# ESP32-PCB-Antenna-USB-Dongle-Motion-Sens.net
KiCad netlist of a schematic drawn in Altium Designer
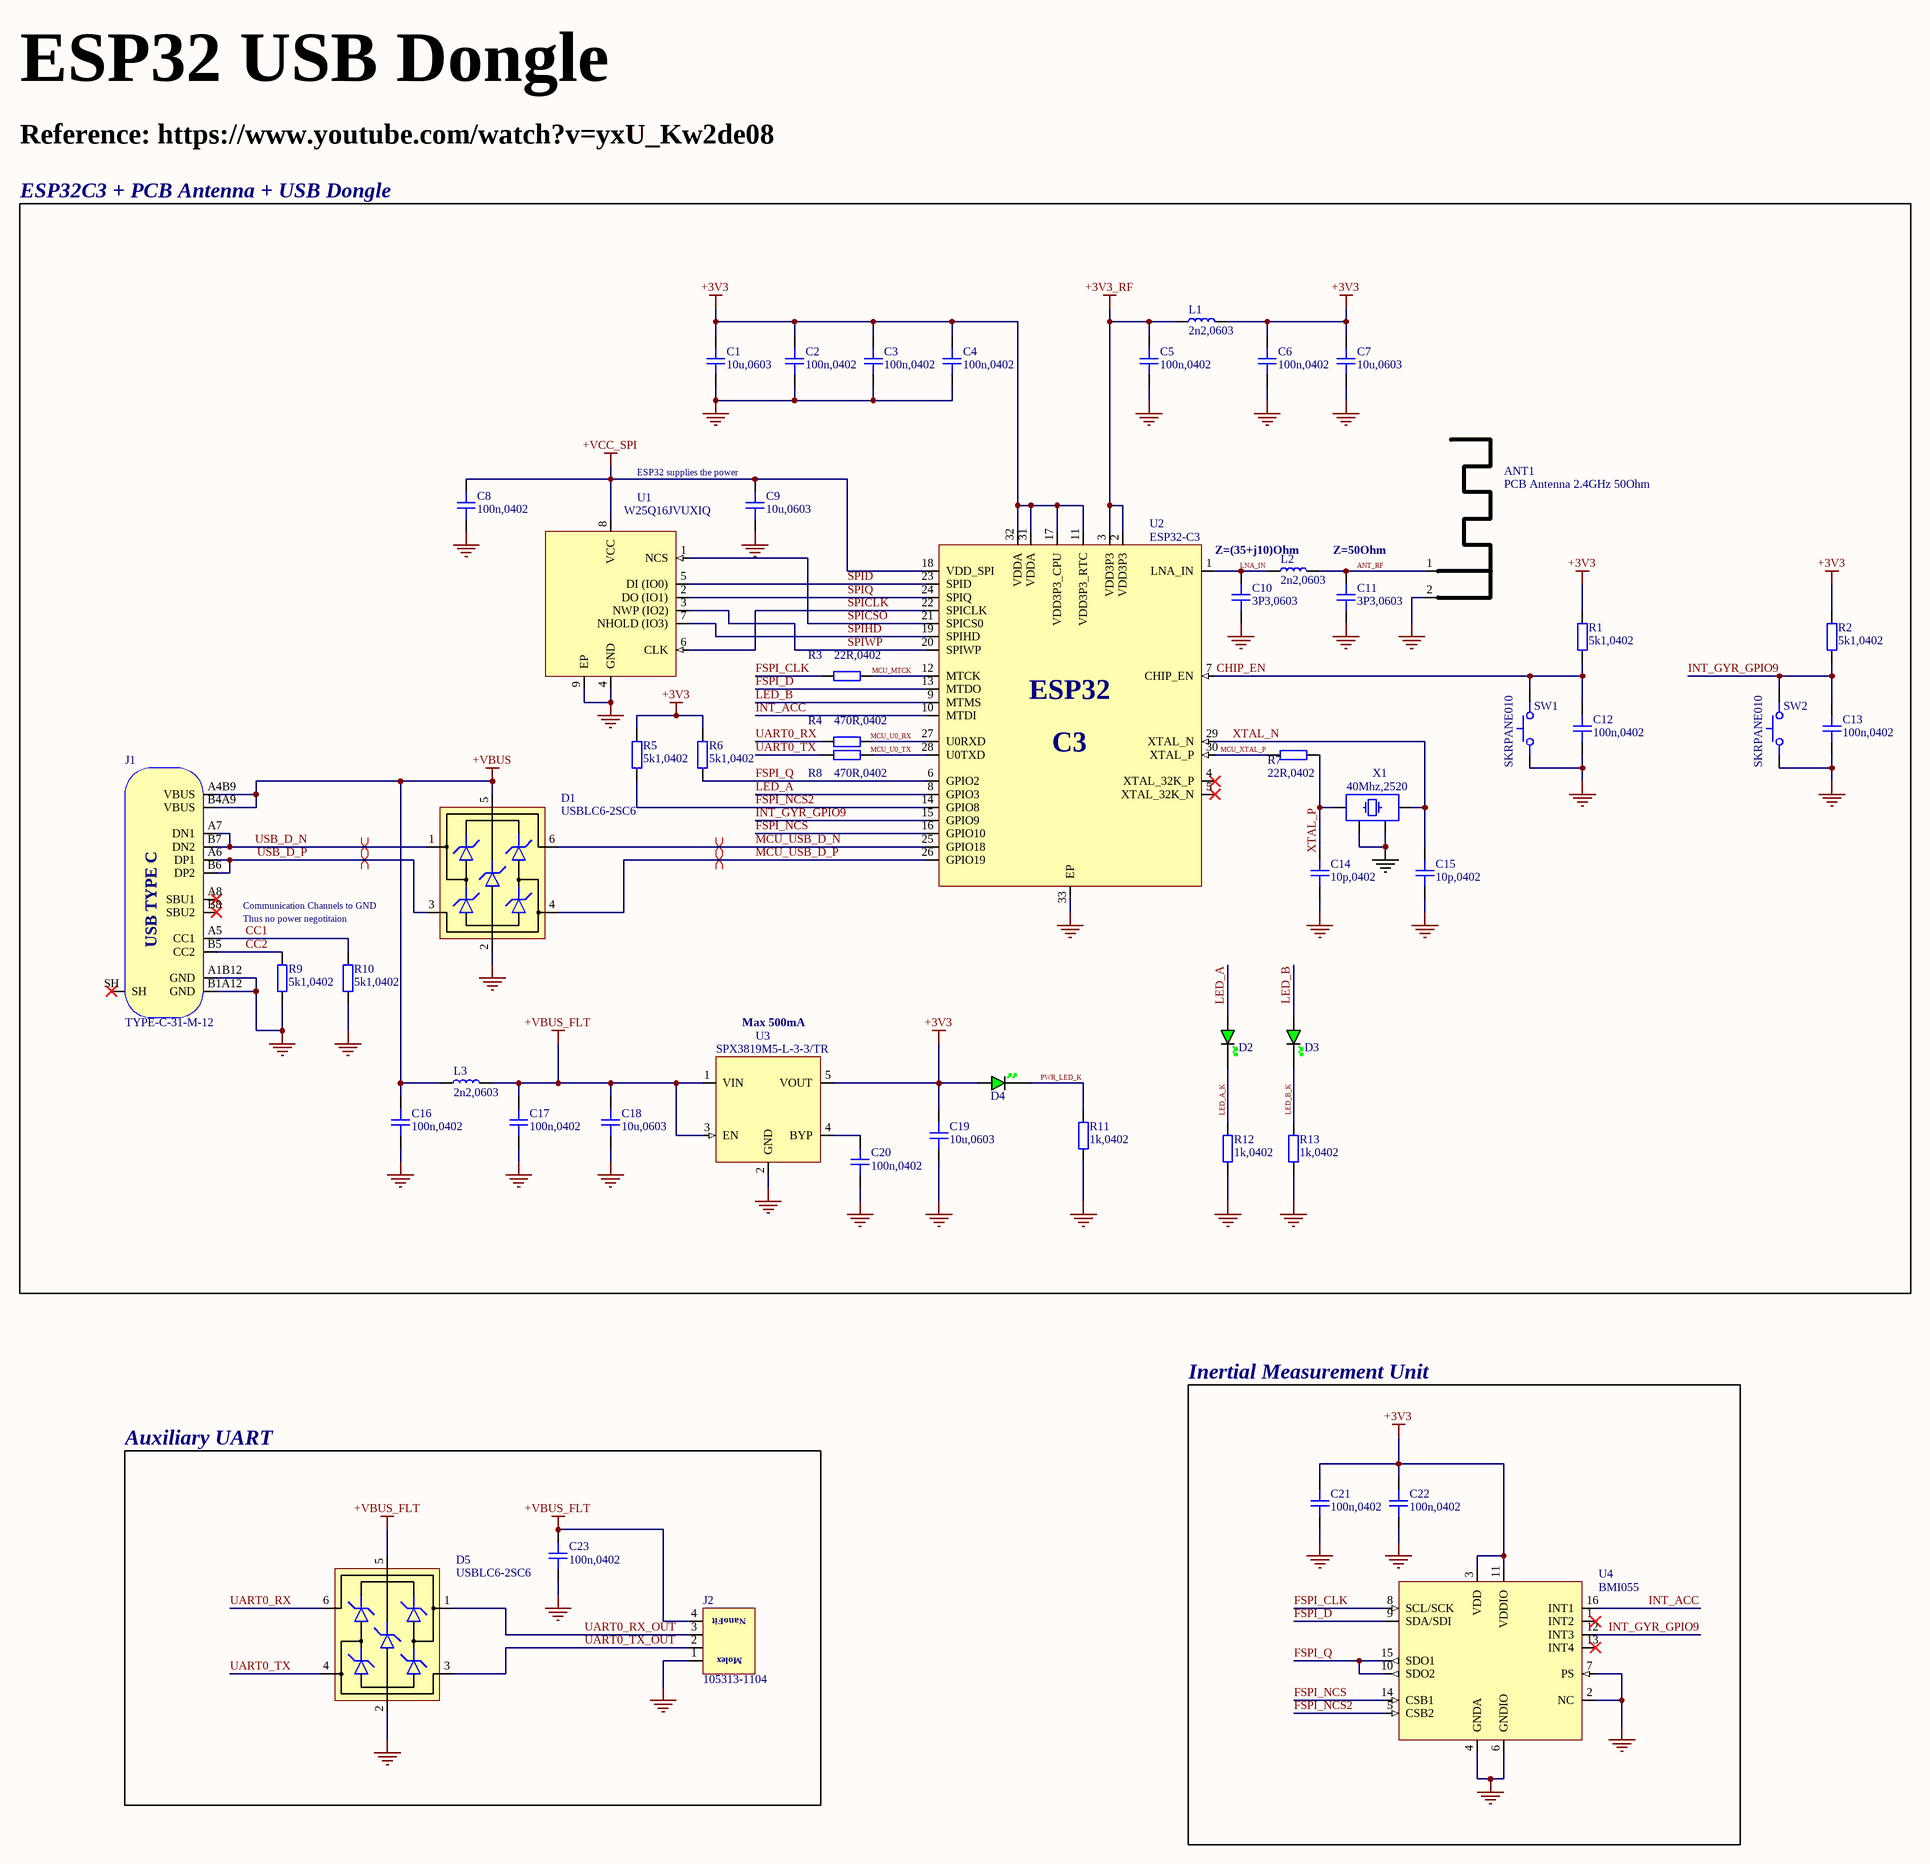
[diagram p0: ESP32-PCB-Antenna-USB-Dongle-Motion-Sensor.SchDoc]

(export (version "E")
  (design (tool "Eeschema 10.0.6"))
  (components
    (comp (ref "ANT1")
      (value "PCB Antenna 2.4GHz 50Ohm")
      (footprint "ANT_IFA_USB_2_4GHZ_50R")
      (description "Inverted F 2.4GHz ISM PCB Antenna 50 Ohm")
      (libsource (lib "Schematic-Lib-PhilsLab") (part "ANT_IFA_USB_2_4GHZ_50R"))
    )
    (comp (ref "C1")
      (value "10u,0603")
      (footprint "CAP_0603")
      (description "Capacitor SMD 0603 25V")
      (libsource (lib "Schematic-Lib-PhilsLab") (part "CAP_0603_25V"))
    )
    (comp (ref "C2")
      (value "100n,0402")
      (footprint "CAP_0402")
      (description "Capacitor SMD 0402 16V")
      (libsource (lib "Schematic-Lib-PhilsLab") (part "CAP_0402_16V"))
    )
    (comp (ref "C3")
      (value "100n,0402")
      (footprint "CAP_0402")
      (description "Capacitor SMD 0402 16V")
      (libsource (lib "Schematic-Lib-PhilsLab") (part "CAP_0402_16V"))
    )
    (comp (ref "C4")
      (value "100n,0402")
      (footprint "CAP_0402")
      (description "Capacitor SMD 0402 16V")
      (libsource (lib "Schematic-Lib-PhilsLab") (part "CAP_0402_16V"))
    )
    (comp (ref "C5")
      (value "100n,0402")
      (footprint "CAP_0402")
      (description "Capacitor SMD 0402 16V")
      (libsource (lib "Schematic-Lib-PhilsLab") (part "CAP_0402_16V"))
    )
    (comp (ref "C6")
      (value "100n,0402")
      (footprint "CAP_0402")
      (description "Capacitor SMD 0402 16V")
      (libsource (lib "Schematic-Lib-PhilsLab") (part "CAP_0402_16V"))
    )
    (comp (ref "C7")
      (value "10u,0603")
      (footprint "CAP_0603")
      (description "Capacitor SMD 0603 25V")
      (libsource (lib "Schematic-Lib-PhilsLab") (part "CAP_0603_25V"))
    )
    (comp (ref "C8")
      (value "100n,0402")
      (footprint "CAP_0402")
      (description "Capacitor SMD 0402 16V")
      (libsource (lib "Schematic-Lib-PhilsLab") (part "CAP_0402_16V"))
    )
    (comp (ref "C9")
      (value "10u,0603")
      (footprint "CAP_0603")
      (description "Capacitor SMD 0603 25V")
      (libsource (lib "Schematic-Lib-PhilsLab") (part "CAP_0603_25V"))
    )
    (comp (ref "C10")
      (value "3P3,0603")
      (footprint "CAP_0603")
      (description "Capacitor SMD 0603 25V")
      (libsource (lib "Schematic-Lib-PhilsLab") (part "CAP_0603_25V"))
    )
    (comp (ref "C11")
      (value "3P3,0603")
      (footprint "CAP_0603")
      (description "Capacitor SMD 0603 25V")
      (libsource (lib "Schematic-Lib-PhilsLab") (part "CAP_0603_25V"))
    )
    (comp (ref "C12")
      (value "100n,0402")
      (footprint "CAP_0402")
      (description "Capacitor SMD 0402 16V")
      (libsource (lib "Schematic-Lib-PhilsLab") (part "CAP_0402_16V"))
    )
    (comp (ref "C13")
      (value "100n,0402")
      (footprint "CAP_0402")
      (description "Capacitor SMD 0402 16V")
      (libsource (lib "Schematic-Lib-PhilsLab") (part "CAP_0402_16V"))
    )
    (comp (ref "C14")
      (value "10p,0402")
      (footprint "CAP_0402")
      (description "Capacitor SMD 0402 16V")
      (libsource (lib "Schematic-Lib-PhilsLab") (part "CAP_0402_16V"))
    )
    (comp (ref "C15")
      (value "10p,0402")
      (footprint "CAP_0402")
      (description "Capacitor SMD 0402 16V")
      (libsource (lib "Schematic-Lib-PhilsLab") (part "CAP_0402_16V"))
    )
    (comp (ref "C16")
      (value "100n,0402")
      (footprint "CAP_0402")
      (description "Capacitor SMD 0402 16V")
      (libsource (lib "Schematic-Lib-PhilsLab") (part "CAP_0402_16V"))
    )
    (comp (ref "C17")
      (value "100n,0402")
      (footprint "CAP_0402")
      (description "Capacitor SMD 0402 16V")
      (libsource (lib "Schematic-Lib-PhilsLab") (part "CAP_0402_16V"))
    )
    (comp (ref "C18")
      (value "10u,0603")
      (footprint "CAP_0603")
      (description "Capacitor SMD 0603 25V")
      (libsource (lib "Schematic-Lib-PhilsLab") (part "CAP_0603_25V"))
    )
    (comp (ref "C19")
      (value "10u,0603")
      (footprint "CAP_0603")
      (description "Capacitor SMD 0603 25V")
      (libsource (lib "Schematic-Lib-PhilsLab") (part "CAP_0603_25V"))
    )
    (comp (ref "C20")
      (value "100n,0402")
      (footprint "CAP_0402")
      (description "Capacitor SMD 0402 16V")
      (libsource (lib "Schematic-Lib-PhilsLab") (part "CAP_0402_16V"))
    )
    (comp (ref "C21")
      (value "100n,0402")
      (footprint "CAP_0402")
      (description "Capacitor SMD 0402 16V")
      (libsource (lib "Schematic-Lib-PhilsLab") (part "CAP_0402_16V"))
    )
    (comp (ref "C22")
      (value "100n,0402")
      (footprint "CAP_0402")
      (description "Capacitor SMD 0402 16V")
      (libsource (lib "Schematic-Lib-PhilsLab") (part "CAP_0402_16V"))
    )
    (comp (ref "C23")
      (value "100n,0402")
      (footprint "CAP_0402")
      (description "Capacitor SMD 0402 16V")
      (libsource (lib "Schematic-Lib-PhilsLab") (part "CAP_0402_16V"))
    )
    (comp (ref "D1")
      (value "USBLC6-2SC6")
      (footprint "SOT-23-6")
      (description "Low-Capacitance ESD Protection USB")
      (fields (field (name "MANUFACTURER") "STMicroelectronics"))
      (libsource (lib "") (part "USBLC6-2SC6_1"))
    )
    (comp (ref "D2")
      (value "GREEN")
      (footprint "LED_0402_GREEN")
      (description "LED 0402 GREEN SMD")
      (libsource (lib "Schematic-Lib-PhilsLab") (part "LED_0402_GREEN"))
    )
    (comp (ref "D3")
      (value "GREEN")
      (footprint "LED_0402_GREEN")
      (description "LED 0402 GREEN SMD")
      (libsource (lib "Schematic-Lib-PhilsLab") (part "LED_0402_GREEN"))
    )
    (comp (ref "D4")
      (value "GREEN")
      (footprint "LED_0402_GREEN")
      (description "LED 0402 GREEN SMD")
      (libsource (lib "Schematic-Lib-PhilsLab") (part "LED_0402_GREEN"))
    )
    (comp (ref "D5")
      (value "USBLC6-2SC6")
      (footprint "SOT-23-6")
      (description "Low-Capacitance ESD Protection USB")
      (fields (field (name "MANUFACTURER") "STMicroelectronics"))
      (libsource (lib "Schematic-Lib-PhilsLab") (part "USBLC6-2SC6"))
    )
    (comp (ref "J1")
      (value "TYPE-C-31-M-12")
      (footprint "TYPE-C-31-M-12")
      (description "USB Type C Connector Horizontal SMT")
      (fields (field (name "MANUFACTURER") "Koren Hroparts"))
      (libsource (lib "Schematic-Lib-PhilsLab") (part "TYPE-C-31-M-12"))
    )
    (comp (ref "J2")
      (value "105313-1104")
      (footprint "105313-1104")
      (fields (field (name "MANUFACTURER") "Molex"))
      (libsource (lib "Schematic-Lib-PhilsLab") (part "105313-1104"))
    )
    (comp (ref "L1")
      (value "2n2,0603")
      (footprint "IND_0603")
      (description "Inductor SMD 0603")
      (libsource (lib "Schematic-Lib-PhilsLab") (part "IND_0603"))
    )
    (comp (ref "L2")
      (value "2n2,0603")
      (footprint "IND_0603")
      (description "Inductor SMD 0603")
      (libsource (lib "Schematic-Lib-PhilsLab") (part "IND_0603"))
    )
    (comp (ref "L3")
      (value "2n2,0603")
      (footprint "IND_0603")
      (description "Inductor SMD 0603")
      (libsource (lib "Schematic-Lib-PhilsLab") (part "IND_0603"))
    )
    (comp (ref "R1")
      (value "5k1,0402")
      (footprint "RES_0402")
      (description "Resistor SMD 0402")
      (libsource (lib "Schematic-Lib-PhilsLab") (part "RES_0402"))
    )
    (comp (ref "R2")
      (value "5k1,0402")
      (footprint "RES_0402")
      (description "Resistor SMD 0402")
      (libsource (lib "Schematic-Lib-PhilsLab") (part "RES_0402"))
    )
    (comp (ref "R3")
      (value "22R,0402")
      (footprint "RES_0402")
      (description "Resistor SMD 0402")
      (libsource (lib "Schematic-Lib-PhilsLab") (part "RES_0402"))
    )
    (comp (ref "R4")
      (value "470R,0402")
      (footprint "RES_0402")
      (description "Resistor SMD 0402")
      (libsource (lib "Schematic-Lib-PhilsLab") (part "RES_0402"))
    )
    (comp (ref "R5")
      (value "5k1,0402")
      (footprint "RES_0402")
      (description "Resistor SMD 0402")
      (libsource (lib "Schematic-Lib-PhilsLab") (part "RES_0402"))
    )
    (comp (ref "R6")
      (value "5k1,0402")
      (footprint "RES_0402")
      (description "Resistor SMD 0402")
      (libsource (lib "Schematic-Lib-PhilsLab") (part "RES_0402"))
    )
    (comp (ref "R7")
      (value "22R,0402")
      (footprint "RES_0402")
      (description "Resistor SMD 0402")
      (libsource (lib "Schematic-Lib-PhilsLab") (part "RES_0402"))
    )
    (comp (ref "R8")
      (value "470R,0402")
      (footprint "RES_0402")
      (description "Resistor SMD 0402")
      (libsource (lib "Schematic-Lib-PhilsLab") (part "RES_0402"))
    )
    (comp (ref "R9")
      (value "5k1,0402")
      (footprint "RES_0402")
      (description "Resistor SMD 0402")
      (libsource (lib "Schematic-Lib-PhilsLab") (part "RES_0402"))
    )
    (comp (ref "R10")
      (value "5k1,0402")
      (footprint "RES_0402")
      (description "Resistor SMD 0402")
      (libsource (lib "Schematic-Lib-PhilsLab") (part "RES_0402"))
    )
    (comp (ref "R11")
      (value "1k,0402")
      (footprint "RES_0402")
      (description "Resistor SMD 0402")
      (libsource (lib "Schematic-Lib-PhilsLab") (part "RES_0402"))
    )
    (comp (ref "R12")
      (value "1k,0402")
      (footprint "RES_0402")
      (description "Resistor SMD 0402")
      (libsource (lib "Schematic-Lib-PhilsLab") (part "RES_0402"))
    )
    (comp (ref "R13")
      (value "1k,0402")
      (footprint "RES_0402")
      (description "Resistor SMD 0402")
      (libsource (lib "Schematic-Lib-PhilsLab") (part "RES_0402"))
    )
    (comp (ref "SW1")
      (value "SKRPANE010")
      (footprint "SKRPANE010")
      (description "Tactile Switch SMD SPST")
      (fields (field (name "MANUFACTURER") "Alps Alpine"))
      (libsource (lib "Schematic-Lib-PhilsLab") (part "SKRPANE010"))
    )
    (comp (ref "SW2")
      (value "SKRPANE010")
      (footprint "SKRPANE010")
      (description "Tactile Switch SMD SPST")
      (fields (field (name "MANUFACTURER") "Alps Alpine"))
      (libsource (lib "Schematic-Lib-PhilsLab") (part "SKRPANE010"))
    )
    (comp (ref "U1")
      (value "W25Q16JVUXIQ")
      (footprint "USON-8-2X3MM")
      (description "16M-BIT SERIAL FLASH MEMORY WITH DUAL/QUAD SPI USON-8")
      (fields (field (name "MANUFACTURER") "Winbond"))
      (libsource (lib "Schematic-Lib-PhilsLab") (part "W25Q16JVUXIQ"))
    )
    (comp (ref "U2")
      (value "ESP32-C3")
      (footprint "QFN32-5x5")
      (fields (field (name "MANUFACTURER") "Espressif"))
      (libsource (lib "Schematic-Lib-PhilsLab") (part "ESP32-C3"))
    )
    (comp (ref "U3")
      (value "SPX3819M5-L-3-3/TR")
      (footprint "SOT-23-5")
      (description "500mA +3.3V Low-Noise LDO Voltage Regulator")
      (fields (field (name "MANUFACTURER") "MaxLinear"))
      (libsource (lib "Schematic-Lib-PhilsLab") (part "SPX3819M5-L-3-3/TR"))
    )
    (comp (ref "U4")
      (value "BMI055")
      (footprint "BMI088")
      (description "Inertial Measurement Unit IMU 6-Axis LGA")
      (fields (field (name "MANUFACTURER") "Bosch"))
      (libsource (lib "Schematic-Lib-PhilsLab") (part "BMI055"))
    )
    (comp (ref "X1")
      (value "40Mhz,2520")
      (footprint "XTAL_2520")
      (description "Crystal SMD 2520")
      (libsource (lib "Schematic-Lib-PhilsLab") (part "XTAL_2520"))
    )
  )
  (nets
    (net (code "1") (name "+3V3") (class "Default")
      (node (ref "C1") (pin "2") (pinfunction "2_2") (pintype "passive"))
      (node (ref "C19") (pin "2") (pinfunction "2_2") (pintype "passive"))
      (node (ref "C2") (pin "2") (pinfunction "2_2") (pintype "passive"))
      (node (ref "C21") (pin "2") (pinfunction "2_2") (pintype "passive"))
      (node (ref "C22") (pin "2") (pinfunction "2_2") (pintype "passive"))
      (node (ref "C3") (pin "2") (pinfunction "2_2") (pintype "passive"))
      (node (ref "C4") (pin "2") (pinfunction "2_2") (pintype "passive"))
      (node (ref "C6") (pin "2") (pinfunction "2_2") (pintype "passive"))
      (node (ref "C7") (pin "2") (pinfunction "2_2") (pintype "passive"))
      (node (ref "D4") (pin "A") (pinfunction "A_A") (pintype "passive"))
      (node (ref "L1") (pin "2") (pinfunction "2_2") (pintype "passive"))
      (node (ref "R1") (pin "2") (pinfunction "2_2") (pintype "passive"))
      (node (ref "R2") (pin "2") (pinfunction "2_2") (pintype "passive"))
      (node (ref "R5") (pin "2") (pinfunction "2_2") (pintype "passive"))
      (node (ref "R6") (pin "2") (pinfunction "2_2") (pintype "passive"))
      (node (ref "U2") (pin "11") (pinfunction "VDD3P3_RTC_11") (pintype "power_in"))
      (node (ref "U2") (pin "17") (pinfunction "VDD3P3_CPU_17") (pintype "power_in"))
      (node (ref "U2") (pin "31") (pinfunction "VDDA_31") (pintype "power_in"))
      (node (ref "U2") (pin "32") (pinfunction "VDDA_32") (pintype "power_in"))
      (node (ref "U3") (pin "5") (pinfunction "VOUT_5") (pintype "power_in"))
      (node (ref "U4") (pin "11") (pinfunction "VDDIO_11") (pintype "power_in"))
      (node (ref "U4") (pin "3") (pinfunction "VDD_3") (pintype "power_in"))
    )
    (net (code "2") (name "+3V3_RF") (class "Default")
      (node (ref "C5") (pin "2") (pinfunction "2_2") (pintype "passive"))
      (node (ref "L1") (pin "1") (pinfunction "1_1") (pintype "passive"))
      (node (ref "U2") (pin "2") (pinfunction "VDD3P3_2") (pintype "power_in"))
      (node (ref "U2") (pin "3") (pinfunction "VDD3P3_3") (pintype "power_in"))
    )
    (net (code "3") (name "+VBUS") (class "Default")
      (node (ref "C16") (pin "2") (pinfunction "2_2") (pintype "passive"))
      (node (ref "D1") (pin "5") (pinfunction "VBUS_5") (pintype "power_in"))
      (node (ref "J1") (pin "A4B9") (pinfunction "VBUS_A4B9") (pintype "power_in"))
      (node (ref "J1") (pin "B4A9") (pinfunction "VBUS_B4A9") (pintype "power_in"))
      (node (ref "L3") (pin "1") (pinfunction "1_1") (pintype "passive"))
    )
    (net (code "4") (name "+VBUS_FLT") (class "Default")
      (node (ref "C17") (pin "2") (pinfunction "2_2") (pintype "passive"))
      (node (ref "C18") (pin "2") (pinfunction "2_2") (pintype "passive"))
      (node (ref "C23") (pin "2") (pinfunction "2_2") (pintype "passive"))
      (node (ref "D5") (pin "5") (pinfunction "VBUS_5") (pintype "power_in"))
      (node (ref "J2") (pin "4") (pinfunction "4_4") (pintype "passive"))
      (node (ref "L3") (pin "2") (pinfunction "2_2") (pintype "passive"))
      (node (ref "U3") (pin "1") (pinfunction "VIN_1") (pintype "power_in"))
      (node (ref "U3") (pin "3") (pinfunction "EN_3") (pintype "input"))
    )
    (net (code "5") (name "+VCC_SPI") (class "Default")
      (node (ref "C8") (pin "2") (pinfunction "2_2") (pintype "passive"))
      (node (ref "C9") (pin "2") (pinfunction "2_2") (pintype "passive"))
      (node (ref "U1") (pin "8") (pinfunction "VCC_8") (pintype "power_in"))
      (node (ref "U2") (pin "18") (pinfunction "VDD_SPI_18") (pintype "power_in"))
    )
    (net (code "6") (name "/ANT_RF") (class "Default")
      (node (ref "ANT1") (pin "1") (pinfunction "RF_1") (pintype "passive"))
      (node (ref "C11") (pin "1") (pinfunction "1_1") (pintype "passive"))
      (node (ref "L2") (pin "2") (pinfunction "2_2") (pintype "passive"))
    )
    (net (code "7") (name "/CC1") (class "Default")
      (node (ref "J1") (pin "A5") (pinfunction "CC1_A5") (pintype "passive"))
      (node (ref "R10") (pin "2") (pinfunction "2_2") (pintype "passive"))
    )
    (net (code "8") (name "/CC2") (class "Default")
      (node (ref "J1") (pin "B5") (pinfunction "CC2_B5") (pintype "tri_state"))
      (node (ref "R9") (pin "2") (pinfunction "2_2") (pintype "passive"))
    )
    (net (code "9") (name "/CHIP_EN") (class "Default")
      (node (ref "C12") (pin "2") (pinfunction "2_2") (pintype "passive"))
      (node (ref "R1") (pin "1") (pinfunction "1_1") (pintype "passive"))
      (node (ref "SW1") (pin "34") (pintype "passive"))
      (node (ref "U2") (pin "7") (pinfunction "CHIP_EN_7") (pintype "input"))
    )
    (net (code "10") (name "/FSPI_CLK") (class "Default")
      (node (ref "R3") (pin "1") (pinfunction "1_1") (pintype "passive"))
      (node (ref "U4") (pin "8") (pinfunction "SCL/SCK_8") (pintype "input"))
    )
    (net (code "11") (name "/FSPI_D") (class "Default")
      (node (ref "U2") (pin "13") (pinfunction "MTDO_13") (pintype "bidirectional"))
      (node (ref "U4") (pin "9") (pinfunction "SDA/SDI_9") (pintype "bidirectional"))
    )
    (net (code "12") (name "/FSPI_NCS") (class "Default")
      (node (ref "U2") (pin "16") (pinfunction "GPIO10_16") (pintype "bidirectional"))
      (node (ref "U4") (pin "14") (pinfunction "CSB1_14") (pintype "input"))
    )
    (net (code "13") (name "/FSPI_NCS2") (class "Default")
      (node (ref "R5") (pin "1") (pinfunction "1_1") (pintype "passive"))
      (node (ref "U2") (pin "14") (pinfunction "GPIO8_14") (pintype "bidirectional"))
      (node (ref "U4") (pin "5") (pinfunction "CSB2_5") (pintype "input"))
    )
    (net (code "14") (name "/FSPI_Q") (class "Default")
      (node (ref "R6") (pin "1") (pinfunction "1_1") (pintype "passive"))
      (node (ref "U2") (pin "6") (pinfunction "GPIO2_6") (pintype "bidirectional"))
      (node (ref "U4") (pin "10") (pinfunction "SDO2_10") (pintype "output"))
      (node (ref "U4") (pin "15") (pinfunction "SDO1_15") (pintype "output"))
    )
    (net (code "15") (name "/INT_ACC") (class "Default")
      (node (ref "U2") (pin "10") (pinfunction "MTDI_10") (pintype "bidirectional"))
      (node (ref "U4") (pin "16") (pinfunction "INT1_16") (pintype "bidirectional"))
    )
    (net (code "16") (name "/INT_GYR_GPIO9") (class "Default")
      (node (ref "C13") (pin "2") (pinfunction "2_2") (pintype "passive"))
      (node (ref "R2") (pin "1") (pinfunction "1_1") (pintype "passive"))
      (node (ref "SW2") (pin "34") (pintype "passive"))
      (node (ref "U2") (pin "15") (pinfunction "GPIO9_15") (pintype "bidirectional"))
      (node (ref "U4") (pin "12") (pinfunction "INT3_12") (pintype "bidirectional"))
    )
    (net (code "17") (name "/LED_A") (class "Default")
      (node (ref "D2") (pin "A") (pinfunction "A_A") (pintype "passive"))
      (node (ref "U2") (pin "8") (pinfunction "GPIO3_8") (pintype "bidirectional"))
    )
    (net (code "18") (name "/LED_A_K") (class "Default")
      (node (ref "D2") (pin "K") (pinfunction "K_K") (pintype "passive"))
      (node (ref "R12") (pin "2") (pinfunction "2_2") (pintype "passive"))
    )
    (net (code "19") (name "/LED_B") (class "Default")
      (node (ref "D3") (pin "A") (pinfunction "A_A") (pintype "passive"))
      (node (ref "U2") (pin "9") (pinfunction "MTMS_9") (pintype "bidirectional"))
    )
    (net (code "20") (name "/LED_B_K") (class "Default")
      (node (ref "D3") (pin "K") (pinfunction "K_K") (pintype "passive"))
      (node (ref "R13") (pin "2") (pinfunction "2_2") (pintype "passive"))
    )
    (net (code "21") (name "/LNA_IN") (class "Default")
      (node (ref "C10") (pin "1") (pinfunction "1_1") (pintype "passive"))
      (node (ref "L2") (pin "1") (pinfunction "1_1") (pintype "passive"))
      (node (ref "U2") (pin "1") (pinfunction "LNA_IN_1") (pintype "bidirectional"))
    )
    (net (code "22") (name "/MCU_MTCK") (class "Default")
      (node (ref "R3") (pin "2") (pinfunction "2_2") (pintype "passive"))
      (node (ref "U2") (pin "12") (pinfunction "MTCK_12") (pintype "bidirectional"))
    )
    (net (code "23") (name "/MCU_U0_RX") (class "Default")
      (node (ref "R4") (pin "2") (pinfunction "2_2") (pintype "passive"))
      (node (ref "U2") (pin "27") (pinfunction "U0RXD_27") (pintype "bidirectional"))
    )
    (net (code "24") (name "/MCU_U0_TX") (class "Default")
      (node (ref "R8") (pin "2") (pinfunction "2_2") (pintype "passive"))
      (node (ref "U2") (pin "28") (pinfunction "U0TXD_28") (pintype "bidirectional"))
    )
    (net (code "25") (name "/MCU_USB_D_N") (class "Default")
      (node (ref "D1") (pin "6") (pinfunction "IO1_6") (pintype "bidirectional"))
      (node (ref "U2") (pin "25") (pinfunction "GPIO18_25") (pintype "bidirectional"))
    )
    (net (code "26") (name "/MCU_USB_D_P") (class "Default")
      (node (ref "D1") (pin "4") (pinfunction "IO2_4") (pintype "bidirectional"))
      (node (ref "U2") (pin "26") (pinfunction "GPIO19_26") (pintype "bidirectional"))
    )
    (net (code "27") (name "/MCU_XTAL_P") (class "Default")
      (node (ref "R7") (pin "1") (pinfunction "1_1") (pintype "passive"))
      (node (ref "U2") (pin "30") (pinfunction "XTAL_P_30") (pintype "input"))
    )
    (net (code "28") (name "/PWR_LED_K") (class "Default")
      (node (ref "D4") (pin "K") (pinfunction "K_K") (pintype "passive"))
      (node (ref "R11") (pin "2") (pinfunction "2_2") (pintype "passive"))
    )
    (net (code "29") (name "/SPICLK") (class "Default")
      (node (ref "U1") (pin "6") (pinfunction "CLK_6") (pintype "input"))
      (node (ref "U2") (pin "22") (pinfunction "SPICLK_22") (pintype "bidirectional"))
    )
    (net (code "30") (name "/SPICSO") (class "Default")
      (node (ref "U1") (pin "1") (pinfunction "NCS_1") (pintype "input"))
      (node (ref "U2") (pin "21") (pinfunction "SPICS0_21") (pintype "bidirectional"))
    )
    (net (code "31") (name "/SPID") (class "Default")
      (node (ref "U1") (pin "5") (pinfunction "DI_(IO0)_5") (pintype "bidirectional"))
      (node (ref "U2") (pin "23") (pinfunction "SPID_23") (pintype "bidirectional"))
    )
    (net (code "32") (name "/SPIHD") (class "Default")
      (node (ref "U1") (pin "7") (pinfunction "NHOLD_(IO3)_7") (pintype "bidirectional"))
      (node (ref "U2") (pin "19") (pinfunction "SPIHD_19") (pintype "bidirectional"))
    )
    (net (code "33") (name "/SPIQ") (class "Default")
      (node (ref "U1") (pin "2") (pinfunction "DO_(IO1)_2") (pintype "bidirectional"))
      (node (ref "U2") (pin "24") (pinfunction "SPIQ_24") (pintype "bidirectional"))
    )
    (net (code "34") (name "/SPIWP") (class "Default")
      (node (ref "U1") (pin "3") (pinfunction "NWP_(IO2)_3") (pintype "bidirectional"))
      (node (ref "U2") (pin "20") (pinfunction "SPIWP_20") (pintype "bidirectional"))
    )
    (net (code "35") (name "/UART0_RX") (class "Default")
      (node (ref "D5") (pin "6") (pinfunction "IO1_6") (pintype "bidirectional"))
      (node (ref "R4") (pin "1") (pinfunction "1_1") (pintype "passive"))
    )
    (net (code "36") (name "/UART0_RX_OUT") (class "Default")
      (node (ref "D5") (pin "1") (pinfunction "IO1_1") (pintype "bidirectional"))
      (node (ref "J2") (pin "3") (pinfunction "3_3") (pintype "passive"))
    )
    (net (code "37") (name "/UART0_TX") (class "Default")
      (node (ref "D5") (pin "4") (pinfunction "IO2_4") (pintype "bidirectional"))
      (node (ref "R8") (pin "1") (pinfunction "1_1") (pintype "passive"))
    )
    (net (code "38") (name "/UART0_TX_OUT") (class "Default")
      (node (ref "D5") (pin "3") (pinfunction "IO2_3") (pintype "bidirectional"))
      (node (ref "J2") (pin "2") (pinfunction "2_2") (pintype "passive"))
    )
    (net (code "39") (name "/USB_D_N") (class "Default")
      (node (ref "D1") (pin "1") (pinfunction "IO1_1") (pintype "bidirectional"))
      (node (ref "J1") (pin "A7") (pinfunction "DN1_A7") (pintype "bidirectional"))
      (node (ref "J1") (pin "B7") (pinfunction "DN2_B7") (pintype "bidirectional"))
    )
    (net (code "40") (name "/USB_D_P") (class "Default")
      (node (ref "D1") (pin "3") (pinfunction "IO2_3") (pintype "bidirectional"))
      (node (ref "J1") (pin "A6") (pinfunction "DP1_A6") (pintype "bidirectional"))
      (node (ref "J1") (pin "B6") (pinfunction "DP2_B6") (pintype "bidirectional"))
    )
    (net (code "41") (name "/XTAL_N") (class "Default")
      (node (ref "C15") (pin "2") (pinfunction "2_2") (pintype "passive"))
      (node (ref "U2") (pin "29") (pinfunction "XTAL_N_29") (pintype "input"))
      (node (ref "X1") (pin "3") (pinfunction "3_3") (pintype "passive"))
    )
    (net (code "42") (name "/XTAL_P") (class "Default")
      (node (ref "C14") (pin "2") (pinfunction "2_2") (pintype "passive"))
      (node (ref "R7") (pin "2") (pinfunction "2_2") (pintype "passive"))
      (node (ref "X1") (pin "1") (pinfunction "1_1") (pintype "passive"))
    )
    (net (code "43") (name "GND") (class "Default")
      (node (ref "ANT1") (pin "2") (pinfunction "GND_2") (pintype "passive"))
      (node (ref "C1") (pin "1") (pinfunction "1_1") (pintype "passive"))
      (node (ref "C10") (pin "2") (pinfunction "2_2") (pintype "passive"))
      (node (ref "C11") (pin "2") (pinfunction "2_2") (pintype "passive"))
      (node (ref "C12") (pin "1") (pinfunction "1_1") (pintype "passive"))
      (node (ref "C13") (pin "1") (pinfunction "1_1") (pintype "passive"))
      (node (ref "C14") (pin "1") (pinfunction "1_1") (pintype "passive"))
      (node (ref "C15") (pin "1") (pinfunction "1_1") (pintype "passive"))
      (node (ref "C16") (pin "1") (pinfunction "1_1") (pintype "passive"))
      (node (ref "C17") (pin "1") (pinfunction "1_1") (pintype "passive"))
      (node (ref "C18") (pin "1") (pinfunction "1_1") (pintype "passive"))
      (node (ref "C19") (pin "1") (pinfunction "1_1") (pintype "passive"))
      (node (ref "C2") (pin "1") (pinfunction "1_1") (pintype "passive"))
      (node (ref "C20") (pin "1") (pinfunction "1_1") (pintype "passive"))
      (node (ref "C21") (pin "1") (pinfunction "1_1") (pintype "passive"))
      (node (ref "C22") (pin "1") (pinfunction "1_1") (pintype "passive"))
      (node (ref "C23") (pin "1") (pinfunction "1_1") (pintype "passive"))
      (node (ref "C3") (pin "1") (pinfunction "1_1") (pintype "passive"))
      (node (ref "C4") (pin "1") (pinfunction "1_1") (pintype "passive"))
      (node (ref "C5") (pin "1") (pinfunction "1_1") (pintype "passive"))
      (node (ref "C6") (pin "1") (pinfunction "1_1") (pintype "passive"))
      (node (ref "C7") (pin "1") (pinfunction "1_1") (pintype "passive"))
      (node (ref "C8") (pin "1") (pinfunction "1_1") (pintype "passive"))
      (node (ref "C9") (pin "1") (pinfunction "1_1") (pintype "passive"))
      (node (ref "D1") (pin "2") (pinfunction "GND_2") (pintype "power_in"))
      (node (ref "D5") (pin "2") (pinfunction "GND_2") (pintype "power_in"))
      (node (ref "J1") (pin "A1B12") (pinfunction "GND_A1B12") (pintype "power_in"))
      (node (ref "J1") (pin "B1A12") (pinfunction "GND_B1A12") (pintype "power_in"))
      (node (ref "J2") (pin "1") (pinfunction "1_1") (pintype "passive"))
      (node (ref "R10") (pin "1") (pinfunction "1_1") (pintype "passive"))
      (node (ref "R11") (pin "1") (pinfunction "1_1") (pintype "passive"))
      (node (ref "R12") (pin "1") (pinfunction "1_1") (pintype "passive"))
      (node (ref "R13") (pin "1") (pinfunction "1_1") (pintype "passive"))
      (node (ref "R9") (pin "1") (pinfunction "1_1") (pintype "passive"))
      (node (ref "SW1") (pin "12") (pintype "passive"))
      (node (ref "SW2") (pin "12") (pintype "passive"))
      (node (ref "U1") (pin "4") (pinfunction "GND_4") (pintype "power_in"))
      (node (ref "U1") (pin "9") (pinfunction "EP_9") (pintype "power_in"))
      (node (ref "U2") (pin "33") (pinfunction "EP_33") (pintype "power_in"))
      (node (ref "U3") (pin "2") (pinfunction "GND_2") (pintype "power_in"))
      (node (ref "U4") (pin "2") (pinfunction "NC_2") (pintype "passive"))
      (node (ref "U4") (pin "4") (pinfunction "GNDA_4") (pintype "power_in"))
      (node (ref "U4") (pin "6") (pinfunction "GNDIO_6") (pintype "power_in"))
      (node (ref "U4") (pin "7") (pinfunction "PS_7") (pintype "input"))
      (node (ref "X1") (pin "2") (pinfunction "2_2") (pintype "passive"))
      (node (ref "X1") (pin "4") (pinfunction "4_4") (pintype "passive"))
    )
    (net (code "44") (name "Net-(U3-BYP)") (class "Default")
      (node (ref "C20") (pin "2") (pinfunction "2_2") (pintype "passive"))
      (node (ref "U3") (pin "4") (pinfunction "BYP_4") (pintype "passive"))
    )
    (net (code "45") (name "unconnected-(J1-PadSH)") (class "Default")
      (node (ref "J1") (pin "SH") (pinfunction "SH_SH") (pintype "power_in+no_connect"))
    )
    (net (code "46") (name "unconnected-(J1-SBU1-PadA8)") (class "Default")
      (node (ref "J1") (pin "A8") (pinfunction "SBU1_A8") (pintype "bidirectional+no_connect"))
    )
    (net (code "47") (name "unconnected-(J1-SBU2-PadB8)") (class "Default")
      (node (ref "J1") (pin "B8") (pinfunction "SBU2_B8") (pintype "bidirectional+no_connect"))
    )
    (net (code "48") (name "unconnected-(U2-XTAL_32K_N-Pad5)") (class "Default")
      (node (ref "U2") (pin "5") (pinfunction "XTAL_32K_N_5") (pintype "bidirectional+no_connect"))
    )
    (net (code "49") (name "unconnected-(U2-XTAL_32K_P-Pad4)") (class "Default")
      (node (ref "U2") (pin "4") (pinfunction "XTAL_32K_P_4") (pintype "bidirectional+no_connect"))
    )
    (net (code "50") (name "unconnected-(U4-INT2-Pad1)") (class "Default")
      (node (ref "U4") (pin "1") (pinfunction "INT2_1") (pintype "bidirectional+no_connect"))
    )
    (net (code "51") (name "unconnected-(U4-INT4-Pad13)") (class "Default")
      (node (ref "U4") (pin "13") (pinfunction "INT4_13") (pintype "bidirectional+no_connect"))
    )
  )
)
